# killsw.net
KiCad netlist of a schematic drawn in EAGLE
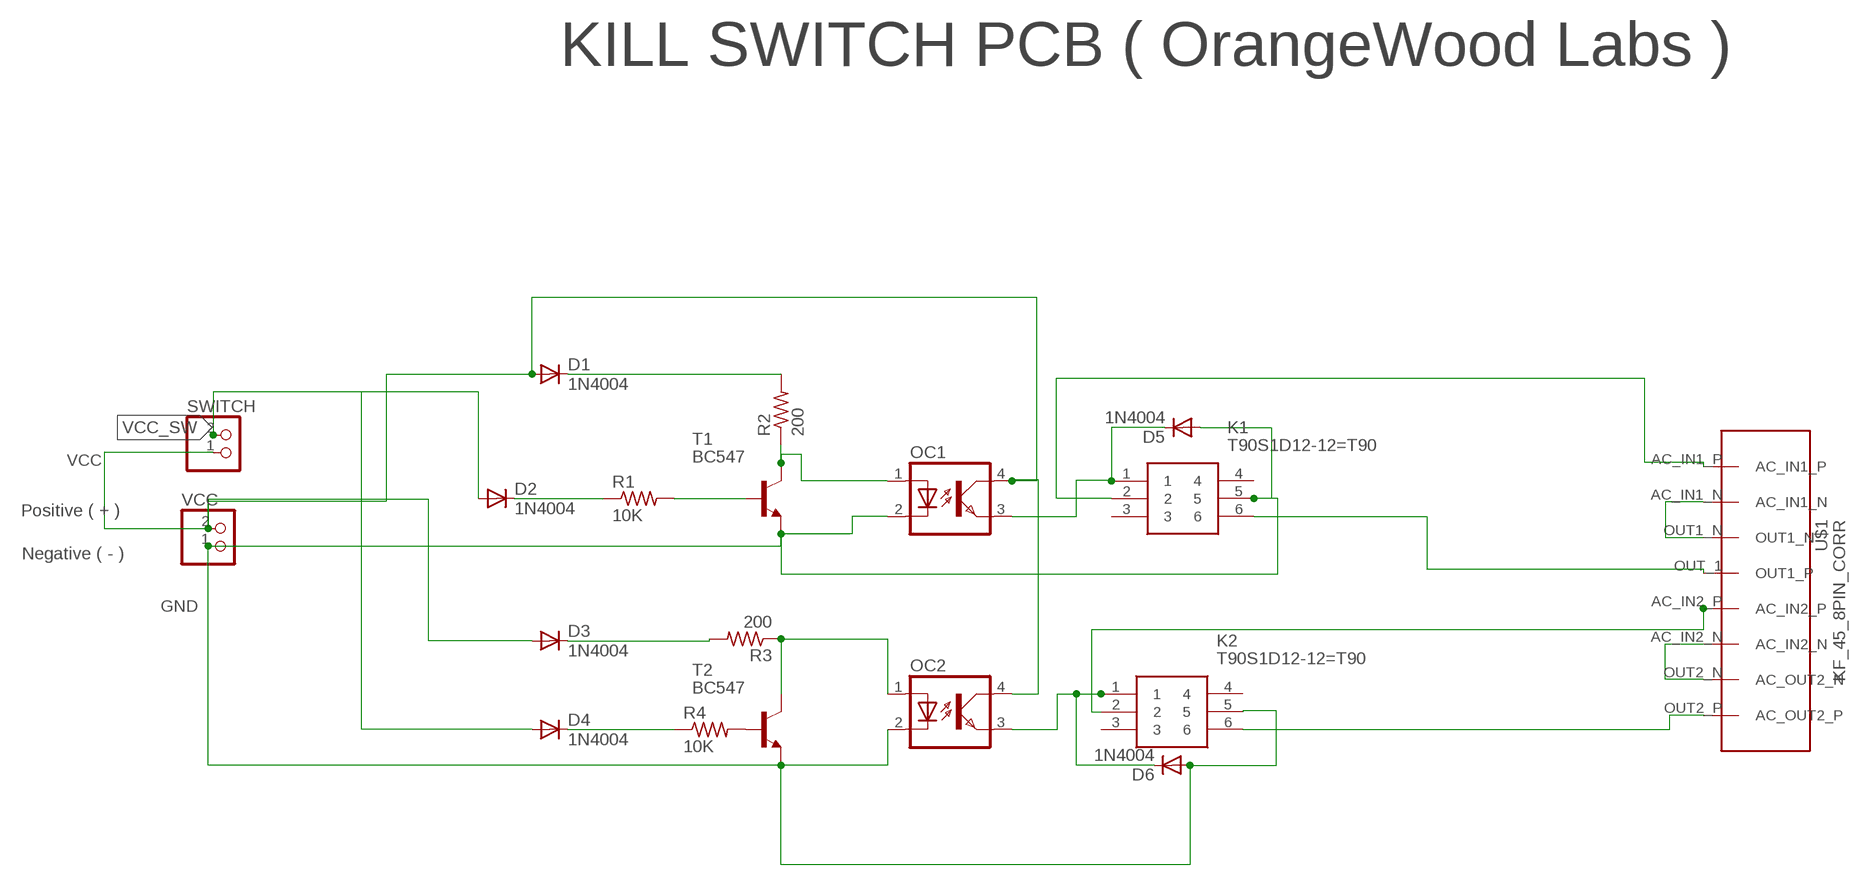
[diagram p0: schematic, sheet 1]

(export (version "E")
  (design (tool "Eeschema 10.0.6"))
  (components
    (comp (ref "D1")
      (value "1N4004")
      (footprint "eagle-import:DO41-10")
      (libsource (lib "eagle-import") (part "1N4004"))
    )
    (comp (ref "D2")
      (value "1N4004")
      (footprint "eagle-import:DO41-10")
      (libsource (lib "eagle-import") (part "1N4004"))
    )
    (comp (ref "D3")
      (value "1N4004")
      (footprint "eagle-import:DO41-10")
      (libsource (lib "eagle-import") (part "1N4004"))
    )
    (comp (ref "D4")
      (value "1N4004")
      (footprint "eagle-import:DO41-10")
      (libsource (lib "eagle-import") (part "1N4004"))
    )
    (comp (ref "D5")
      (value "1N4004")
      (footprint "eagle-import:DO41-10")
      (libsource (lib "eagle-import") (part "1N4004"))
    )
    (comp (ref "D6")
      (value "1N4004")
      (footprint "eagle-import:DO41-10")
      (libsource (lib "eagle-import") (part "1N4004"))
    )
    (comp (ref "K1")
      (value "T90S1D12-12=T90")
      (footprint "eagle-import:T90S1D12-12=T90")
      (fields (field (name "RS_PART_NUMBER") "1640200"))
      (libsource (lib "eagle-import") (part "T90S1D12-12=T90"))
    )
    (comp (ref "K2")
      (value "T90S1D12-12=T90")
      (footprint "eagle-import:T90S1D12-12=T90")
      (fields (field (name "RS_PART_NUMBER") "1640200"))
      (libsource (lib "eagle-import") (part "T90S1D12-12=T90"))
    )
    (comp (ref "OC1")
      (value "PC817")
      (footprint "eagle-import:DIL04")
      (libsource (lib "eagle-import") (part "PC817"))
    )
    (comp (ref "OC2")
      (value "PC817")
      (footprint "eagle-import:DIL04")
      (libsource (lib "eagle-import") (part "PC817"))
    )
    (comp (ref "R1")
      (value "10K")
      (footprint "eagle-import:0204_7")
      (libsource (lib "eagle-import") (part "R-US_0204/7"))
    )
    (comp (ref "R2")
      (value "200")
      (footprint "eagle-import:0204_7")
      (libsource (lib "eagle-import") (part "R-US_0204/7"))
    )
    (comp (ref "R3")
      (value "200")
      (footprint "eagle-import:0204_7")
      (libsource (lib "eagle-import") (part "R-US_0204/7"))
    )
    (comp (ref "R4")
      (value "10K")
      (footprint "eagle-import:0204_7")
      (libsource (lib "eagle-import") (part "R-US_0204/7"))
    )
    (comp (ref "SWITCH")
      (value "JST_2PIN-THM")
      (footprint "eagle-import:JST-PH-2-THM")
      (libsource (lib "eagle-import") (part "JST_2PIN-THM"))
    )
    (comp (ref "T1")
      (value "BC547")
      (footprint "eagle-import:TO92")
      (libsource (lib "eagle-import") (part "BC547"))
    )
    (comp (ref "T2")
      (value "BC547")
      (footprint "eagle-import:TO92")
      (libsource (lib "eagle-import") (part "BC547"))
    )
    (comp (ref "U$1")
      (value "KF_45_8PIN_CORR")
      (footprint "eagle-import:KF-45")
      (libsource (lib "eagle-import") (part "KF_45_8PIN_CORR"))
    )
    (comp (ref "VCC")
      (value "JST_2PIN-THM")
      (footprint "eagle-import:JST-PH-2-THM")
      (libsource (lib "eagle-import") (part "JST_2PIN-THM"))
    )
  )
  (nets
    (net (code "1") (name "/GND") (class "Default")
      (node (ref "D5") (pin "A") (pinfunction "A_A") (pintype "passive"))
      (node (ref "D6") (pin "A") (pinfunction "A_A") (pintype "passive"))
      (node (ref "K1") (pin "5") (pinfunction "5_5") (pintype "bidirectional"))
      (node (ref "K2") (pin "5") (pinfunction "5_5") (pintype "bidirectional"))
      (node (ref "OC1") (pin "2") (pinfunction "C_2") (pintype "passive"))
      (node (ref "OC2") (pin "2") (pinfunction "C_2") (pintype "passive"))
      (node (ref "T1") (pin "1") (pinfunction "E_1") (pintype "passive"))
      (node (ref "T2") (pin "1") (pinfunction "E_1") (pintype "passive"))
      (node (ref "VCC") (pin "1") (pinfunction "2_1") (pintype "passive"))
    )
    (net (code "2") (name "/VCC") (class "Default")
      (node (ref "D1") (pin "A") (pinfunction "A_A") (pintype "passive"))
      (node (ref "D3") (pin "A") (pinfunction "A_A") (pintype "passive"))
      (node (ref "OC1") (pin "4") (pinfunction "COL_4") (pintype "passive"))
      (node (ref "OC2") (pin "4") (pinfunction "COL_4") (pintype "passive"))
      (node (ref "SWITCH") (pin "1") (pinfunction "2_1") (pintype "passive"))
      (node (ref "VCC") (pin "2") (pinfunction "1_2") (pintype "passive"))
    )
    (net (code "3") (name "Net-(D1-PadC)") (class "Default")
      (node (ref "D1") (pin "C") (pinfunction "C_C") (pintype "passive"))
      (node (ref "R2") (pin "2") (pinfunction "2_2") (pintype "passive"))
    )
    (net (code "4") (name "Net-(D2-PadC)") (class "Default")
      (node (ref "D2") (pin "C") (pinfunction "C_C") (pintype "passive"))
      (node (ref "R1") (pin "1") (pinfunction "1_1") (pintype "passive"))
    )
    (net (code "5") (name "Net-(D3-PadC)") (class "Default")
      (node (ref "D3") (pin "C") (pinfunction "C_C") (pintype "passive"))
      (node (ref "R3") (pin "2") (pinfunction "2_2") (pintype "passive"))
    )
    (net (code "6") (name "Net-(D4-PadC)") (class "Default")
      (node (ref "D4") (pin "C") (pinfunction "C_C") (pintype "passive"))
      (node (ref "R4") (pin "1") (pinfunction "1_1") (pintype "passive"))
    )
    (net (code "7") (name "Net-(K1-Pad2)") (class "Default")
      (node (ref "K1") (pin "2") (pinfunction "2_2") (pintype "bidirectional"))
      (node (ref "U$1") (pin "AC_IN1_P") (pinfunction "AC_IN1_P_AC_IN1_P") (pintype "bidirectional"))
    )
    (net (code "8") (name "Net-(K2-Pad2)") (class "Default")
      (node (ref "K2") (pin "2") (pinfunction "2_2") (pintype "bidirectional"))
      (node (ref "U$1") (pin "AC_IN2_P") (pinfunction "AC_IN2_P_AC_IN2_P") (pintype "bidirectional"))
    )
    (net (code "9") (name "Net-(OC1-A)") (class "Default")
      (node (ref "OC1") (pin "1") (pinfunction "A_1") (pintype "passive"))
      (node (ref "R2") (pin "1") (pinfunction "1_1") (pintype "passive"))
      (node (ref "T1") (pin "3") (pinfunction "C_3") (pintype "passive"))
    )
    (net (code "10") (name "Net-(OC1-EMIT)") (class "Default")
      (node (ref "D5") (pin "C") (pinfunction "C_C") (pintype "passive"))
      (node (ref "K1") (pin "1") (pinfunction "1_1") (pintype "bidirectional"))
      (node (ref "OC1") (pin "3") (pinfunction "EMIT_3") (pintype "passive"))
    )
    (net (code "11") (name "Net-(OC2-A)") (class "Default")
      (node (ref "OC2") (pin "1") (pinfunction "A_1") (pintype "passive"))
      (node (ref "R3") (pin "1") (pinfunction "1_1") (pintype "passive"))
      (node (ref "T2") (pin "3") (pinfunction "C_3") (pintype "passive"))
    )
    (net (code "12") (name "Net-(OC2-EMIT)") (class "Default")
      (node (ref "D6") (pin "C") (pinfunction "C_C") (pintype "passive"))
      (node (ref "K2") (pin "1") (pinfunction "1_1") (pintype "bidirectional"))
      (node (ref "OC2") (pin "3") (pinfunction "EMIT_3") (pintype "passive"))
    )
    (net (code "13") (name "Net-(T1-B)") (class "Default")
      (node (ref "R1") (pin "2") (pinfunction "2_2") (pintype "passive"))
      (node (ref "T1") (pin "2") (pinfunction "B_2") (pintype "passive"))
    )
    (net (code "14") (name "Net-(T2-B)") (class "Default")
      (node (ref "R4") (pin "2") (pinfunction "2_2") (pintype "passive"))
      (node (ref "T2") (pin "2") (pinfunction "B_2") (pintype "passive"))
    )
    (net (code "15") (name "Net-(U$1-AC_OUT2_N)") (class "Default")
      (node (ref "U$1") (pin "AC_IN2_N") (pinfunction "AC_IN2_N_AC_IN2_N") (pintype "bidirectional"))
      (node (ref "U$1") (pin "OUT2_N") (pinfunction "AC_OUT2_N_OUT2_N") (pintype "bidirectional"))
    )
    (net (code "16") (name "Net-(U$1-AC_OUT2_P)") (class "Default")
      (node (ref "K2") (pin "6") (pinfunction "6_6") (pintype "bidirectional"))
      (node (ref "U$1") (pin "OUT2_P") (pinfunction "AC_OUT2_P_OUT2_P") (pintype "bidirectional"))
    )
    (net (code "17") (name "Net-(U$1-OUT1_P)") (class "Default")
      (node (ref "K1") (pin "6") (pinfunction "6_6") (pintype "bidirectional"))
      (node (ref "U$1") (pin "OUT_1") (pinfunction "OUT1_P_OUT_1") (pintype "bidirectional"))
    )
    (net (code "18") (name "Net-(U$1-PadAC_IN1_N)") (class "Default")
      (node (ref "U$1") (pin "AC_IN1_N") (pinfunction "AC_IN1_N_AC_IN1_N") (pintype "bidirectional"))
      (node (ref "U$1") (pin "OUT1_N") (pinfunction "OUT1_N_OUT1_N") (pintype "bidirectional"))
    )
    (net (code "19") (name "VCC_SW") (class "Default")
      (node (ref "D2") (pin "A") (pinfunction "A_A") (pintype "passive"))
      (node (ref "D4") (pin "A") (pinfunction "A_A") (pintype "passive"))
      (node (ref "SWITCH") (pin "2") (pinfunction "1_2") (pintype "passive"))
    )
    (net (code "20") (name "unconnected-(K1-Pad3)") (class "Default")
      (node (ref "K1") (pin "3") (pinfunction "3_3") (pintype "bidirectional"))
    )
    (net (code "21") (name "unconnected-(K1-Pad4)") (class "Default")
      (node (ref "K1") (pin "4") (pinfunction "4_4") (pintype "bidirectional"))
    )
    (net (code "22") (name "unconnected-(K2-Pad3)") (class "Default")
      (node (ref "K2") (pin "3") (pinfunction "3_3") (pintype "bidirectional"))
    )
    (net (code "23") (name "unconnected-(K2-Pad4)") (class "Default")
      (node (ref "K2") (pin "4") (pinfunction "4_4") (pintype "bidirectional"))
    )
  )
)
